# MaTouch_Devkit_LED_Screen_V1_2.net
KiCad netlist of a schematic drawn in EAGLE
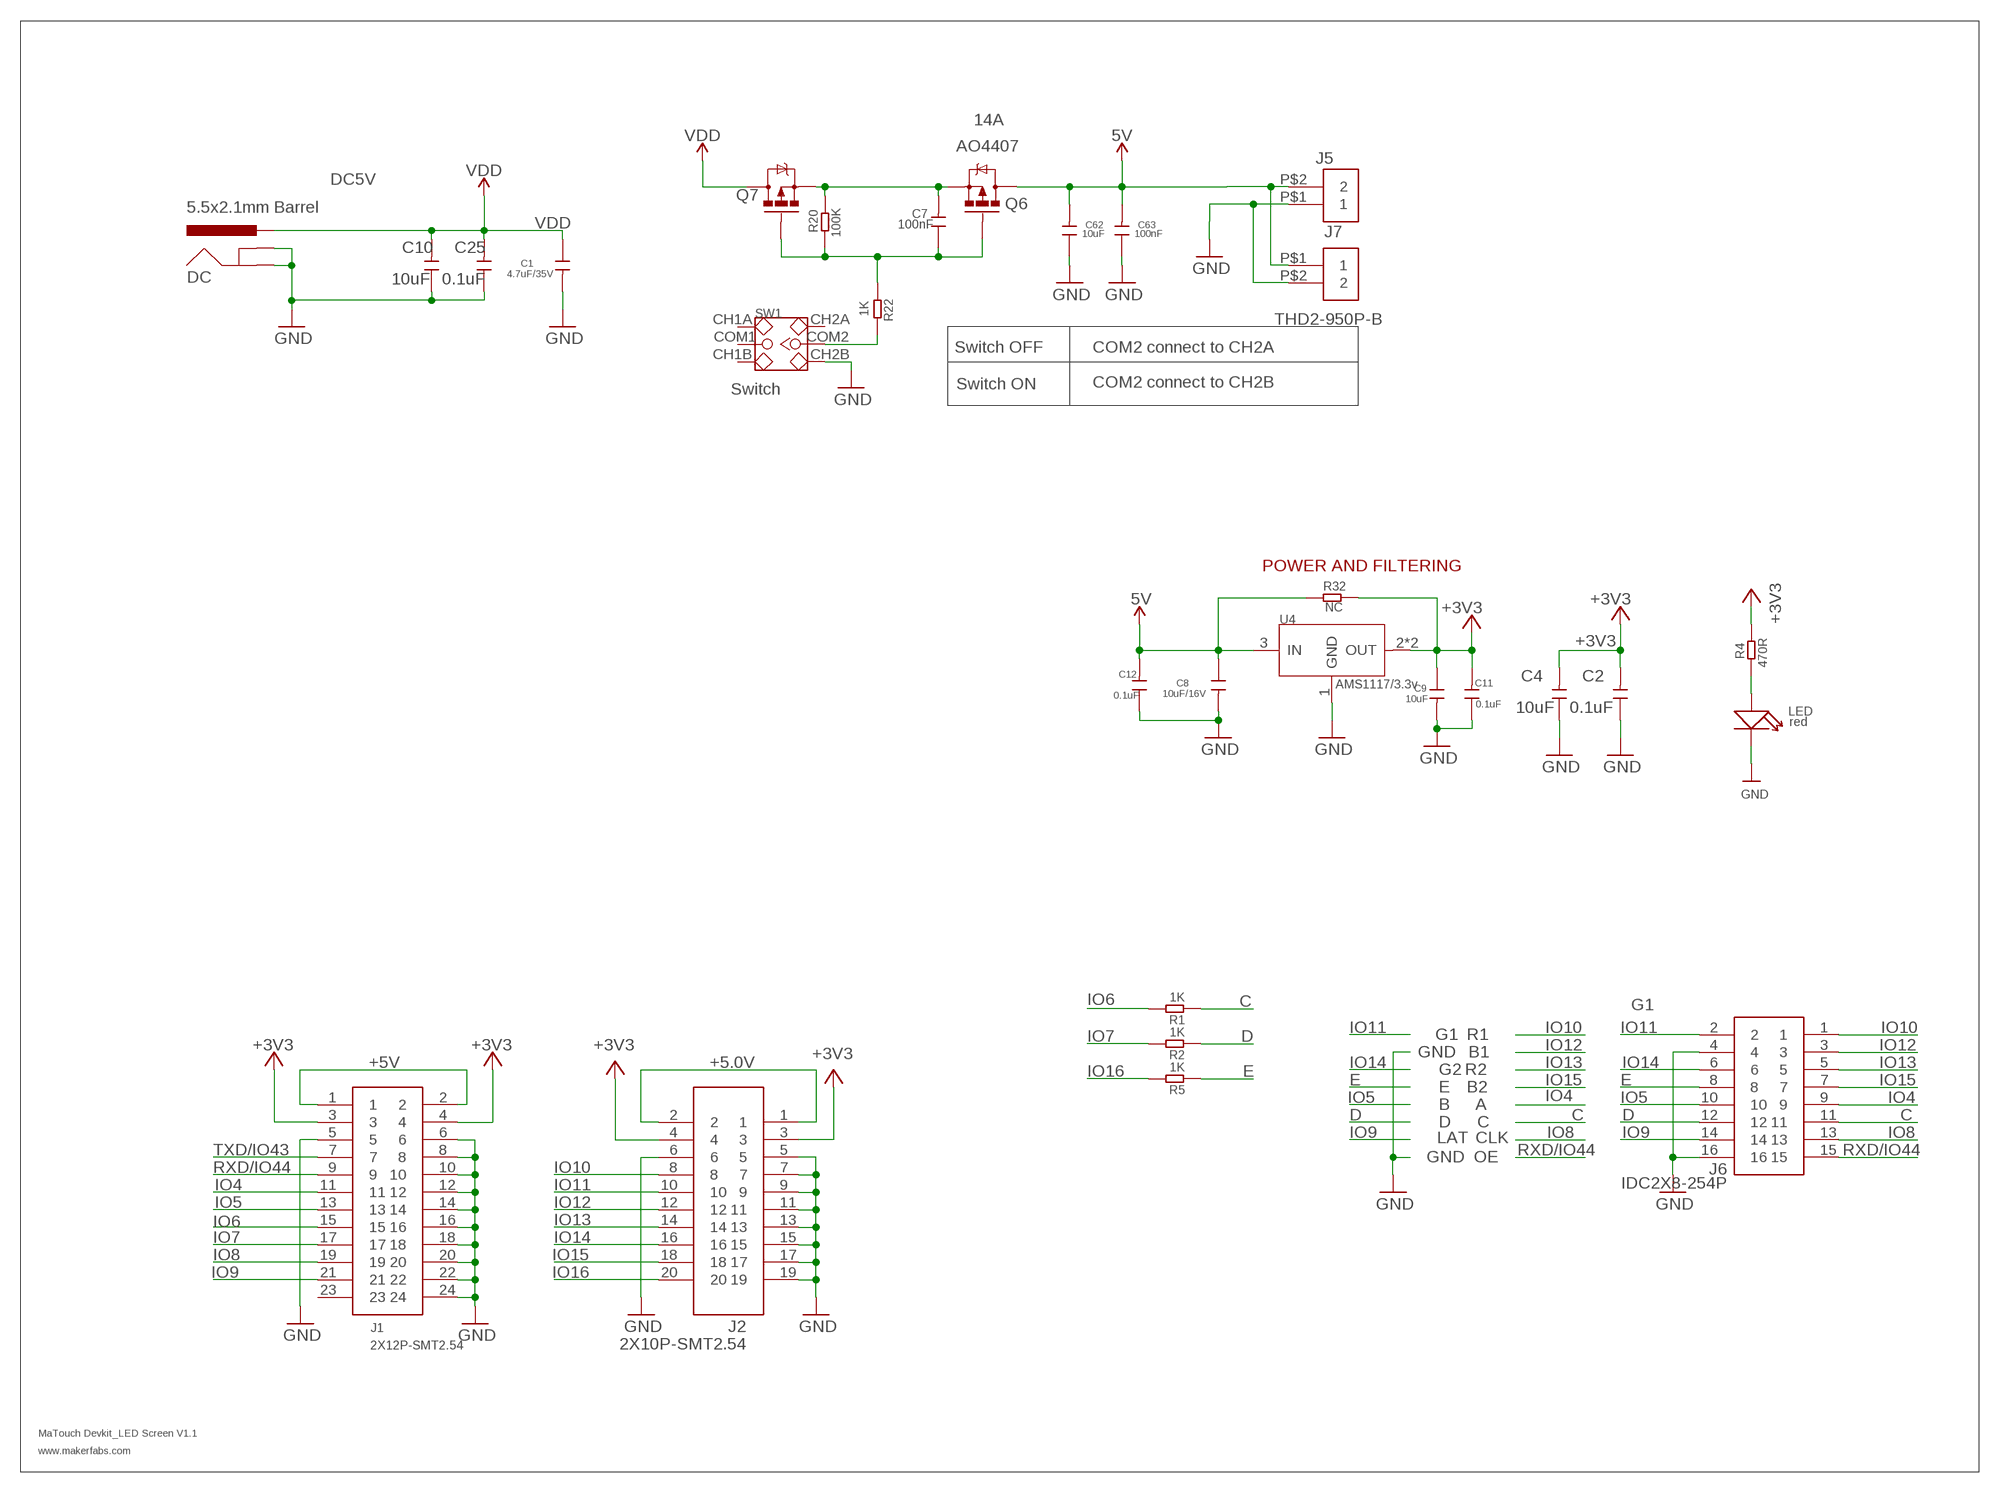
[diagram p0: schematic, sheet 1]

(export (version "E")
  (design (tool "Eeschema 10.0.6"))
  (components
    (comp (ref "C1")
      (value "4.7uF/35V")
      (footprint "eagle-import:0603")
      (libsource (lib "eagle-import") (part "C-0603"))
    )
    (comp (ref "C2")
      (value "0.1uF")
      (footprint "eagle-import:0603")
      (libsource (lib "eagle-import") (part "C-0603"))
    )
    (comp (ref "C4")
      (value "10uF")
      (footprint "eagle-import:0603")
      (libsource (lib "eagle-import") (part "C-0603"))
    )
    (comp (ref "C7")
      (value "100nF")
      (footprint "eagle-import:0603")
      (libsource (lib "eagle-import") (part "C-0603"))
    )
    (comp (ref "C8")
      (value "10uF/16V")
      (footprint "eagle-import:0603")
      (libsource (lib "eagle-import") (part "C-0603"))
    )
    (comp (ref "C9")
      (value "10uF")
      (footprint "eagle-import:0603")
      (libsource (lib "eagle-import") (part "C-0603"))
    )
    (comp (ref "C10")
      (value "10uF")
      (footprint "eagle-import:0603")
      (libsource (lib "eagle-import") (part "C-0603"))
    )
    (comp (ref "C11")
      (value "0.1uF")
      (footprint "eagle-import:0603")
      (libsource (lib "eagle-import") (part "C-0603"))
    )
    (comp (ref "C12")
      (value "0.1uF")
      (footprint "eagle-import:0603")
      (libsource (lib "eagle-import") (part "C-0603"))
    )
    (comp (ref "C25")
      (value "0.1uF")
      (footprint "eagle-import:0603")
      (libsource (lib "eagle-import") (part "C-0603"))
    )
    (comp (ref "C62")
      (value "10uF")
      (footprint "eagle-import:0603")
      (libsource (lib "eagle-import") (part "C-0603"))
    )
    (comp (ref "C63")
      (value "100nF")
      (footprint "eagle-import:0603")
      (libsource (lib "eagle-import") (part "C-0603"))
    )
    (comp (ref "DC")
      (value "5.5x2.1mm Barrel")
      (footprint "eagle-import:POWER_JACK_SMD")
      (libsource (lib "eagle-import") (part "POWER_JACKSMD"))
    )
    (comp (ref "J1")
      (value "2X12P-SMT2.54")
      (footprint "eagle-import:2X12P-SMT2.54")
      (libsource (lib "eagle-import") (part "2X12P-SMT2.54"))
    )
    (comp (ref "J2")
      (value "2X10P-SMT2.54")
      (footprint "eagle-import:2X10P-SMT2.54")
      (libsource (lib "eagle-import") (part "2X10P-SMT2.54"))
    )
    (comp (ref "J5")
      (value "THD2-950P-2050L1620W1670H")
      (footprint "eagle-import:THD2-950P-2050L1620W1670H")
      (libsource (lib "eagle-import") (part "THD2-950P-2050L1620W1670H"))
    )
    (comp (ref "J6")
      (value "IDC2X8-254P")
      (footprint "eagle-import:IDC2X8-254P-2792L1330W890H")
      (libsource (lib "eagle-import") (part "IDC2X8-254P-2792L1330W890H"))
    )
    (comp (ref "J7")
      (value "THD2-950P-B")
      (footprint "eagle-import:THD2-950P-2100L1580W1780H")
      (libsource (lib "eagle-import") (part "THD2-950P-B"))
    )
    (comp (ref "LED")
      (value "red")
      (footprint "eagle-import:DISCRETE_LED-0603")
      (libsource (lib "eagle-import") (part "DISCRETE_LED0603"))
    )
    (comp (ref "Q6")
      (value "MOSFET-PCHANNELFDS6675")
      (footprint "eagle-import:SO08")
      (libsource (lib "eagle-import") (part "MOSFET-PCHANNELFDS6675"))
    )
    (comp (ref "Q7")
      (value "MOSFET-PCHANNELFDS6675")
      (footprint "eagle-import:SO08")
      (libsource (lib "eagle-import") (part "MOSFET-PCHANNELFDS6675"))
    )
    (comp (ref "R1")
      (value "1K")
      (footprint "eagle-import:R0603")
      (libsource (lib "eagle-import") (part "R-0603"))
    )
    (comp (ref "R2")
      (value "1K")
      (footprint "eagle-import:R0603")
      (libsource (lib "eagle-import") (part "R-0603"))
    )
    (comp (ref "R4")
      (value "470R")
      (footprint "eagle-import:R0603")
      (libsource (lib "eagle-import") (part "R-0603"))
    )
    (comp (ref "R5")
      (value "1K")
      (footprint "eagle-import:R0603")
      (libsource (lib "eagle-import") (part "R-0603"))
    )
    (comp (ref "R20")
      (value "100K")
      (footprint "eagle-import:R0603")
      (libsource (lib "eagle-import") (part "R-0603"))
    )
    (comp (ref "R22")
      (value "1K")
      (footprint "eagle-import:R0603")
      (libsource (lib "eagle-import") (part "R-0603"))
    )
    (comp (ref "R32")
      (value "NC")
      (footprint "eagle-import:R0603")
      (libsource (lib "eagle-import") (part "R-0603"))
    )
    (comp (ref "SW1")
      (value "SWITCH-2CH-6P'90D'")
      (footprint "eagle-import:6P-2CH-2.54-9.0X3.6-90D")
      (libsource (lib "eagle-import") (part "SWITCH-2CH-6P'90D'"))
    )
    (comp (ref "U4")
      (value "AMS1117/3.3v")
      (footprint "eagle-import:SOT89")
      (libsource (lib "eagle-import") (part "LD1117'SOT89'"))
    )
  )
  (nets
    (net (code "1") (name "+3V3") (class "Default")
      (node (ref "C11") (pin "2") (pinfunction "2_2") (pintype "passive"))
      (node (ref "C2") (pin "2") (pinfunction "2_2") (pintype "passive"))
      (node (ref "C4") (pin "2") (pinfunction "2_2") (pintype "passive"))
      (node (ref "C9") (pin "1") (pinfunction "1_1") (pintype "passive"))
      (node (ref "J1") (pin "3") (pinfunction "3_3") (pintype "bidirectional"))
      (node (ref "J1") (pin "4") (pinfunction "4_4") (pintype "bidirectional"))
      (node (ref "J2") (pin "3") (pinfunction "3_3") (pintype "bidirectional"))
      (node (ref "J2") (pin "4") (pinfunction "4_4") (pintype "bidirectional"))
      (node (ref "R32") (pin "2") (pinfunction "2_2") (pintype "passive"))
      (node (ref "R4") (pin "2") (pinfunction "2_2") (pintype "passive"))
      (node (ref "U4") (pin "2") (pinfunction "OUT_2") (pintype "bidirectional"))
      (node (ref "U4") (pin "4") (pinfunction "OUT_4") (pintype "bidirectional"))
    )
    (net (code "2") (name "/+5.0V") (class "Default")
      (node (ref "J2") (pin "1") (pinfunction "1_1") (pintype "bidirectional"))
      (node (ref "J2") (pin "2") (pinfunction "2_2") (pintype "bidirectional"))
    )
    (net (code "3") (name "/+5V") (class "Default")
      (node (ref "J1") (pin "1") (pinfunction "1_1") (pintype "bidirectional"))
      (node (ref "J1") (pin "2") (pinfunction "2_2") (pintype "bidirectional"))
    )
    (net (code "4") (name "/C") (class "Default")
      (node (ref "J6") (pin "11") (pinfunction "11_11") (pintype "bidirectional"))
      (node (ref "R1") (pin "1") (pinfunction "1_1") (pintype "passive"))
    )
    (net (code "5") (name "/D") (class "Default")
      (node (ref "J6") (pin "12") (pinfunction "12_12") (pintype "bidirectional"))
      (node (ref "R2") (pin "1") (pinfunction "1_1") (pintype "passive"))
    )
    (net (code "6") (name "/E") (class "Default")
      (node (ref "J6") (pin "8") (pinfunction "8_8") (pintype "bidirectional"))
      (node (ref "R5") (pin "1") (pinfunction "1_1") (pintype "passive"))
    )
    (net (code "7") (name "/IO4") (class "Default")
      (node (ref "J1") (pin "11") (pinfunction "11_11") (pintype "bidirectional"))
      (node (ref "J6") (pin "9") (pinfunction "9_9") (pintype "bidirectional"))
    )
    (net (code "8") (name "/IO5") (class "Default")
      (node (ref "J1") (pin "13") (pinfunction "13_13") (pintype "bidirectional"))
      (node (ref "J6") (pin "10") (pinfunction "10_10") (pintype "bidirectional"))
    )
    (net (code "9") (name "/IO6") (class "Default")
      (node (ref "J1") (pin "15") (pinfunction "15_15") (pintype "bidirectional"))
      (node (ref "R1") (pin "2") (pinfunction "2_2") (pintype "passive"))
    )
    (net (code "10") (name "/IO7") (class "Default")
      (node (ref "J1") (pin "17") (pinfunction "17_17") (pintype "bidirectional"))
      (node (ref "R2") (pin "2") (pinfunction "2_2") (pintype "passive"))
    )
    (net (code "11") (name "/IO8") (class "Default")
      (node (ref "J1") (pin "19") (pinfunction "19_19") (pintype "bidirectional"))
      (node (ref "J6") (pin "13") (pinfunction "13_13") (pintype "bidirectional"))
    )
    (net (code "12") (name "/IO9") (class "Default")
      (node (ref "J1") (pin "21") (pinfunction "21_21") (pintype "bidirectional"))
      (node (ref "J6") (pin "14") (pinfunction "14_14") (pintype "bidirectional"))
    )
    (net (code "13") (name "/IO10") (class "Default")
      (node (ref "J2") (pin "8") (pinfunction "8_8") (pintype "bidirectional"))
      (node (ref "J6") (pin "1") (pinfunction "1_1") (pintype "bidirectional"))
    )
    (net (code "14") (name "/IO11") (class "Default")
      (node (ref "J2") (pin "10") (pinfunction "10_10") (pintype "bidirectional"))
      (node (ref "J6") (pin "2") (pinfunction "2_2") (pintype "bidirectional"))
    )
    (net (code "15") (name "/IO12") (class "Default")
      (node (ref "J2") (pin "12") (pinfunction "12_12") (pintype "bidirectional"))
      (node (ref "J6") (pin "3") (pinfunction "3_3") (pintype "bidirectional"))
    )
    (net (code "16") (name "/IO13") (class "Default")
      (node (ref "J2") (pin "14") (pinfunction "14_14") (pintype "bidirectional"))
      (node (ref "J6") (pin "5") (pinfunction "5_5") (pintype "bidirectional"))
    )
    (net (code "17") (name "/IO14") (class "Default")
      (node (ref "J2") (pin "16") (pinfunction "16_16") (pintype "bidirectional"))
      (node (ref "J6") (pin "6") (pinfunction "6_6") (pintype "bidirectional"))
    )
    (net (code "18") (name "/IO15") (class "Default")
      (node (ref "J2") (pin "18") (pinfunction "18_18") (pintype "bidirectional"))
      (node (ref "J6") (pin "7") (pinfunction "7_7") (pintype "bidirectional"))
    )
    (net (code "19") (name "/IO16") (class "Default")
      (node (ref "J2") (pin "20") (pinfunction "20_20") (pintype "bidirectional"))
      (node (ref "R5") (pin "2") (pinfunction "2_2") (pintype "passive"))
    )
    (net (code "20") (name "/RXD{slash}IO44") (class "Default")
      (node (ref "J1") (pin "9") (pinfunction "9_9") (pintype "bidirectional"))
      (node (ref "J6") (pin "15") (pinfunction "15_15") (pintype "bidirectional"))
    )
    (net (code "21") (name "/TXD{slash}IO43") (class "Default")
      (node (ref "J1") (pin "7") (pinfunction "7_7") (pintype "bidirectional"))
    )
    (net (code "22") (name "5V") (class "Default")
      (node (ref "C12") (pin "2") (pinfunction "2_2") (pintype "passive"))
      (node (ref "C62") (pin "2") (pinfunction "2_2") (pintype "passive"))
      (node (ref "C63") (pin "2") (pinfunction "2_2") (pintype "passive"))
      (node (ref "C8") (pin "1") (pinfunction "1_1") (pintype "passive"))
      (node (ref "J5") (pin "P$2") (pinfunction "2_P$2") (pintype "bidirectional"))
      (node (ref "J7") (pin "P$1") (pinfunction "1_P$1") (pintype "bidirectional"))
      (node (ref "Q6") (pin "5") (pinfunction "D_5") (pintype "passive"))
      (node (ref "Q6") (pin "6") (pinfunction "D_6") (pintype "passive"))
      (node (ref "Q6") (pin "7") (pinfunction "D_7") (pintype "passive"))
      (node (ref "Q6") (pin "8") (pinfunction "D_8") (pintype "passive"))
      (node (ref "R32") (pin "1") (pinfunction "1_1") (pintype "passive"))
      (node (ref "U4") (pin "3") (pinfunction "IN_3") (pintype "bidirectional"))
    )
    (net (code "23") (name "GND") (class "Default")
      (node (ref "C1") (pin "2") (pinfunction "2_2") (pintype "passive"))
      (node (ref "C10") (pin "1") (pinfunction "1_1") (pintype "passive"))
      (node (ref "C11") (pin "1") (pinfunction "1_1") (pintype "passive"))
      (node (ref "C12") (pin "1") (pinfunction "1_1") (pintype "passive"))
      (node (ref "C2") (pin "1") (pinfunction "1_1") (pintype "passive"))
      (node (ref "C25") (pin "1") (pinfunction "1_1") (pintype "passive"))
      (node (ref "C4") (pin "1") (pinfunction "1_1") (pintype "passive"))
      (node (ref "C62") (pin "1") (pinfunction "1_1") (pintype "passive"))
      (node (ref "C63") (pin "1") (pinfunction "1_1") (pintype "passive"))
      (node (ref "C8") (pin "2") (pinfunction "2_2") (pintype "passive"))
      (node (ref "C9") (pin "2") (pinfunction "2_2") (pintype "passive"))
      (node (ref "DC") (pin "GND") (pinfunction "GNDBREAK_GND") (pintype "bidirectional"))
      (node (ref "DC") (pin "P$4") (pinfunction "GND_P$4") (pintype "bidirectional"))
      (node (ref "J1") (pin "10") (pinfunction "10_10") (pintype "bidirectional"))
      (node (ref "J1") (pin "12") (pinfunction "12_12") (pintype "bidirectional"))
      (node (ref "J1") (pin "14") (pinfunction "14_14") (pintype "bidirectional"))
      (node (ref "J1") (pin "16") (pinfunction "16_16") (pintype "bidirectional"))
      (node (ref "J1") (pin "18") (pinfunction "18_18") (pintype "bidirectional"))
      (node (ref "J1") (pin "20") (pinfunction "20_20") (pintype "bidirectional"))
      (node (ref "J1") (pin "22") (pinfunction "22_22") (pintype "bidirectional"))
      (node (ref "J1") (pin "24") (pinfunction "24_24") (pintype "bidirectional"))
      (node (ref "J1") (pin "5") (pinfunction "5_5") (pintype "bidirectional"))
      (node (ref "J1") (pin "6") (pinfunction "6_6") (pintype "bidirectional"))
      (node (ref "J1") (pin "8") (pinfunction "8_8") (pintype "bidirectional"))
      (node (ref "J2") (pin "11") (pinfunction "11_11") (pintype "bidirectional"))
      (node (ref "J2") (pin "13") (pinfunction "13_13") (pintype "bidirectional"))
      (node (ref "J2") (pin "15") (pinfunction "15_15") (pintype "bidirectional"))
      (node (ref "J2") (pin "17") (pinfunction "17_17") (pintype "bidirectional"))
      (node (ref "J2") (pin "19") (pinfunction "19_19") (pintype "bidirectional"))
      (node (ref "J2") (pin "5") (pinfunction "5_5") (pintype "bidirectional"))
      (node (ref "J2") (pin "6") (pinfunction "6_6") (pintype "bidirectional"))
      (node (ref "J2") (pin "7") (pinfunction "7_7") (pintype "bidirectional"))
      (node (ref "J2") (pin "9") (pinfunction "9_9") (pintype "bidirectional"))
      (node (ref "J5") (pin "P$1") (pinfunction "1_P$1") (pintype "bidirectional"))
      (node (ref "J6") (pin "16") (pinfunction "16_16") (pintype "bidirectional"))
      (node (ref "J6") (pin "4") (pinfunction "4_4") (pintype "bidirectional"))
      (node (ref "J7") (pin "P$2") (pinfunction "2_P$2") (pintype "bidirectional"))
      (node (ref "LED") (pin "-") (pinfunction "-_-") (pintype "passive"))
      (node (ref "SW1") (pin "CH2B") (pinfunction "CH2B_CH2B") (pintype "bidirectional"))
      (node (ref "U4") (pin "1") (pinfunction "GND_1") (pintype "bidirectional"))
    )
    (net (code "24") (name "Net-(C7-Pad2)") (class "Default")
      (node (ref "C7") (pin "2") (pinfunction "2_2") (pintype "passive"))
      (node (ref "Q6") (pin "1") (pinfunction "S_1") (pintype "passive"))
      (node (ref "Q6") (pin "2") (pinfunction "S_2") (pintype "passive"))
      (node (ref "Q6") (pin "3") (pinfunction "S_3") (pintype "passive"))
      (node (ref "Q7") (pin "1") (pinfunction "S_1") (pintype "passive"))
      (node (ref "Q7") (pin "2") (pinfunction "S_2") (pintype "passive"))
      (node (ref "Q7") (pin "3") (pinfunction "S_3") (pintype "passive"))
      (node (ref "R20") (pin "1") (pinfunction "1_1") (pintype "passive"))
    )
    (net (code "25") (name "Net-(LED-Pad+)") (class "Default")
      (node (ref "LED") (pin "+") (pinfunction "+_+") (pintype "passive"))
      (node (ref "R4") (pin "1") (pinfunction "1_1") (pintype "passive"))
    )
    (net (code "26") (name "Net-(Q6-G)") (class "Default")
      (node (ref "C7") (pin "1") (pinfunction "1_1") (pintype "passive"))
      (node (ref "Q6") (pin "4") (pinfunction "G_4") (pintype "passive"))
      (node (ref "Q7") (pin "4") (pinfunction "G_4") (pintype "passive"))
      (node (ref "R20") (pin "2") (pinfunction "2_2") (pintype "passive"))
      (node (ref "R22") (pin "2") (pinfunction "2_2") (pintype "passive"))
    )
    (net (code "27") (name "Net-(R22-Pad1)") (class "Default")
      (node (ref "R22") (pin "1") (pinfunction "1_1") (pintype "passive"))
      (node (ref "SW1") (pin "COM2") (pinfunction "COM2_COM2") (pintype "bidirectional"))
    )
    (net (code "28") (name "VDD") (class "Default")
      (node (ref "C1") (pin "1") (pinfunction "1_1") (pintype "passive"))
      (node (ref "C10") (pin "2") (pinfunction "2_2") (pintype "passive"))
      (node (ref "C25") (pin "2") (pinfunction "2_2") (pintype "passive"))
      (node (ref "DC") (pin "VIN0") (pinfunction "PWR_VIN0") (pintype "bidirectional"))
      (node (ref "Q7") (pin "5") (pinfunction "D_5") (pintype "passive"))
      (node (ref "Q7") (pin "6") (pinfunction "D_6") (pintype "passive"))
      (node (ref "Q7") (pin "7") (pinfunction "D_7") (pintype "passive"))
      (node (ref "Q7") (pin "8") (pinfunction "D_8") (pintype "passive"))
    )
    (net (code "29") (name "unconnected-(J1-Pad23)") (class "Default")
      (node (ref "J1") (pin "23") (pinfunction "23_23") (pintype "bidirectional"))
    )
    (net (code "30") (name "unconnected-(SW1-PadCH1A)") (class "Default")
      (node (ref "SW1") (pin "CH1A") (pinfunction "CH1A_CH1A") (pintype "bidirectional"))
    )
    (net (code "31") (name "unconnected-(SW1-PadCH1B)") (class "Default")
      (node (ref "SW1") (pin "CH1B") (pinfunction "CH1B_CH1B") (pintype "bidirectional"))
    )
    (net (code "32") (name "unconnected-(SW1-PadCH2A)") (class "Default")
      (node (ref "SW1") (pin "CH2A") (pinfunction "CH2A_CH2A") (pintype "bidirectional"))
    )
    (net (code "33") (name "unconnected-(SW1-PadCOM1)") (class "Default")
      (node (ref "SW1") (pin "COM1") (pinfunction "COM1_COM1") (pintype "bidirectional"))
    )
  )
)
